# plant.net
KiCad netlist of a schematic drawn in EAGLE
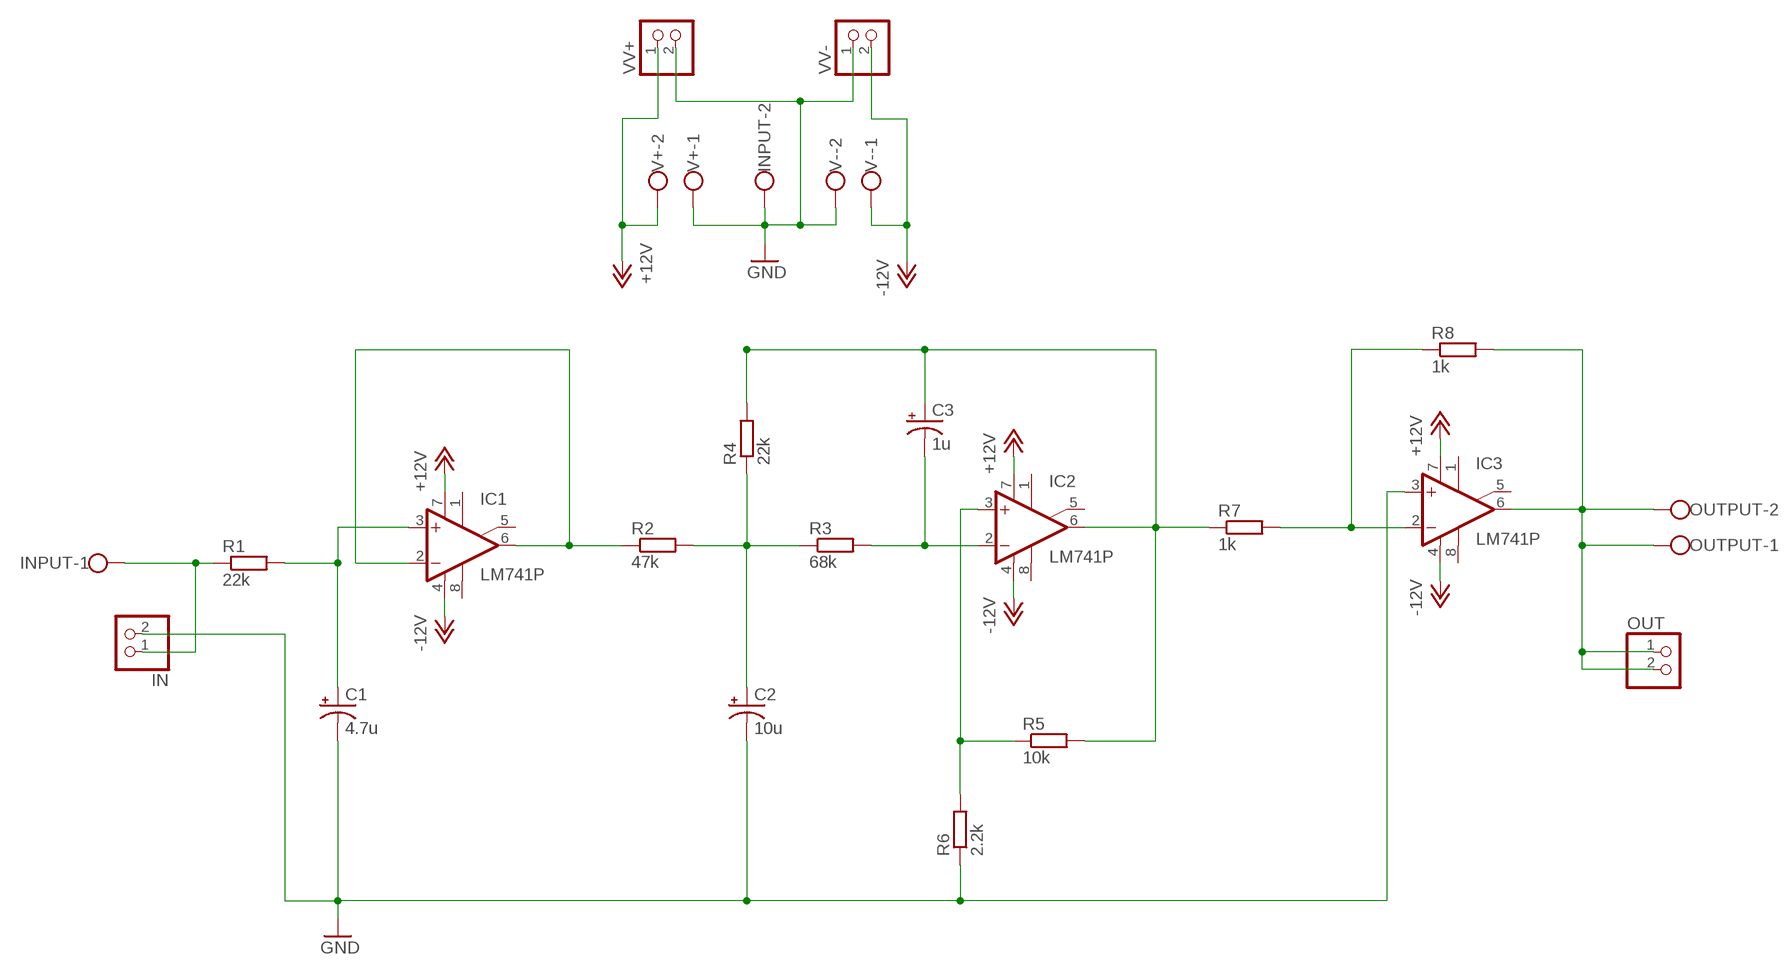
[diagram p0: schematic, sheet 1]

(export (version "E")
  (design (tool "Eeschema 10.0.6"))
  (components
    (comp (ref "C1")
      (value "4.7u")
      (footprint "eagle-import:E2,5-6")
      (libsource (lib "eagle-import") (part "CPOL-USE2.5-6"))
    )
    (comp (ref "C2")
      (value "10u")
      (footprint "eagle-import:E2,5-6")
      (libsource (lib "eagle-import") (part "CPOL-USE2.5-6"))
    )
    (comp (ref "C3")
      (value "1u")
      (footprint "eagle-import:E2,5-6")
      (libsource (lib "eagle-import") (part "CPOL-USE2.5-6"))
    )
    (comp (ref "IC1")
      (value "LM741P")
      (footprint "eagle-import:DIL08")
      (libsource (lib "eagle-import") (part "741PLM"))
    )
    (comp (ref "IC2")
      (value "LM741P")
      (footprint "eagle-import:DIL08")
      (libsource (lib "eagle-import") (part "741PLM"))
    )
    (comp (ref "IC3")
      (value "LM741P")
      (footprint "eagle-import:DIL08")
      (libsource (lib "eagle-import") (part "741PLM"))
    )
    (comp (ref "IN")
      (value "PINHD-1X2")
      (footprint "eagle-import:1X02")
      (libsource (lib "eagle-import") (part "PINHD-1X2"))
    )
    (comp (ref "INPUT")
      (value "W237-102")
      (footprint "eagle-import:W237-102")
      (fields (field (name "MPN") "237-102"))
      (libsource (lib "eagle-import") (part "W237-102"))
    )
    (comp (ref "OUT")
      (value "PINHD-1X2")
      (footprint "eagle-import:1X02")
      (libsource (lib "eagle-import") (part "PINHD-1X2"))
    )
    (comp (ref "OUTPUT")
      (value "W237-102")
      (footprint "eagle-import:W237-102")
      (fields (field (name "MPN") "237-102"))
      (libsource (lib "eagle-import") (part "W237-102"))
    )
    (comp (ref "R1")
      (value "22k")
      (footprint "eagle-import:0207_7")
      (libsource (lib "eagle-import") (part "R-EU_0207/7"))
    )
    (comp (ref "R2")
      (value "47k")
      (footprint "eagle-import:0207_7")
      (libsource (lib "eagle-import") (part "R-EU_0207/7"))
    )
    (comp (ref "R3")
      (value "68k")
      (footprint "eagle-import:0207_7")
      (libsource (lib "eagle-import") (part "R-EU_0207/7"))
    )
    (comp (ref "R4")
      (value "22k")
      (footprint "eagle-import:0207_7")
      (libsource (lib "eagle-import") (part "R-EU_0207/7"))
    )
    (comp (ref "R5")
      (value "10k")
      (footprint "eagle-import:0207_7")
      (libsource (lib "eagle-import") (part "R-EU_0207/7"))
    )
    (comp (ref "R6")
      (value "2.2k")
      (footprint "eagle-import:0207_7")
      (libsource (lib "eagle-import") (part "R-EU_0207/7"))
    )
    (comp (ref "R7")
      (value "1k")
      (footprint "eagle-import:0207_7")
      (libsource (lib "eagle-import") (part "R-EU_0207/7"))
    )
    (comp (ref "R8")
      (value "1k")
      (footprint "eagle-import:0207_7")
      (libsource (lib "eagle-import") (part "R-EU_0207/7"))
    )
    (comp (ref "V+")
      (value "W237-102")
      (footprint "eagle-import:W237-102")
      (fields (field (name "MPN") "237-102"))
      (libsource (lib "eagle-import") (part "W237-102"))
    )
    (comp (ref "V-")
      (value "W237-102")
      (footprint "eagle-import:W237-102")
      (fields (field (name "MPN") "237-102"))
      (libsource (lib "eagle-import") (part "W237-102"))
    )
    (comp (ref "VV+")
      (value "PINHD-1X2")
      (footprint "eagle-import:1X02")
      (libsource (lib "eagle-import") (part "PINHD-1X2"))
    )
    (comp (ref "VV-")
      (value "PINHD-1X2")
      (footprint "eagle-import:1X02")
      (libsource (lib "eagle-import") (part "PINHD-1X2"))
    )
  )
  (nets
    (net (code "1") (name "+12V") (class "Default")
      (node (ref "IC1") (pin "7") (pinfunction "V+_7") (pintype "power_in"))
      (node (ref "IC2") (pin "7") (pinfunction "V+_7") (pintype "power_in"))
      (node (ref "IC3") (pin "7") (pinfunction "V+_7") (pintype "power_in"))
      (node (ref "V+") (pin "2") (pinfunction "KL_2") (pintype "passive"))
      (node (ref "VV+") (pin "1") (pinfunction "1_1") (pintype "passive"))
    )
    (net (code "2") (name "-12V") (class "Default")
      (node (ref "IC1") (pin "4") (pinfunction "V-_4") (pintype "power_in"))
      (node (ref "IC2") (pin "4") (pinfunction "V-_4") (pintype "power_in"))
      (node (ref "IC3") (pin "4") (pinfunction "V-_4") (pintype "power_in"))
      (node (ref "V-") (pin "1") (pinfunction "KL_1") (pintype "passive"))
      (node (ref "VV-") (pin "2") (pinfunction "2_2") (pintype "passive"))
    )
    (net (code "3") (name "GND") (class "Default")
      (node (ref "C1") (pin "-") (pinfunction "-_-") (pintype "passive"))
      (node (ref "C2") (pin "-") (pinfunction "-_-") (pintype "passive"))
      (node (ref "IC3") (pin "3") (pinfunction "+IN_3") (pintype "input"))
      (node (ref "IN") (pin "2") (pinfunction "2_2") (pintype "passive"))
      (node (ref "INPUT") (pin "2") (pinfunction "KL_2") (pintype "passive"))
      (node (ref "R6") (pin "1") (pinfunction "1_1") (pintype "passive"))
      (node (ref "V+") (pin "1") (pinfunction "KL_1") (pintype "passive"))
      (node (ref "V-") (pin "2") (pinfunction "KL_2") (pintype "passive"))
      (node (ref "VV+") (pin "2") (pinfunction "2_2") (pintype "passive"))
      (node (ref "VV-") (pin "1") (pinfunction "1_1") (pintype "passive"))
    )
    (net (code "4") (name "Net-(C2-Pad+)") (class "Default")
      (node (ref "C2") (pin "+") (pinfunction "+_+") (pintype "passive"))
      (node (ref "R2") (pin "2") (pinfunction "2_2") (pintype "passive"))
      (node (ref "R3") (pin "1") (pinfunction "1_1") (pintype "passive"))
      (node (ref "R4") (pin "1") (pinfunction "1_1") (pintype "passive"))
    )
    (net (code "5") (name "Net-(IC1-+IN)") (class "Default")
      (node (ref "C1") (pin "+") (pinfunction "+_+") (pintype "passive"))
      (node (ref "IC1") (pin "3") (pinfunction "+IN_3") (pintype "input"))
      (node (ref "R1") (pin "2") (pinfunction "2_2") (pintype "passive"))
    )
    (net (code "6") (name "Net-(IC1--IN)") (class "Default")
      (node (ref "IC1") (pin "2") (pinfunction "-IN_2") (pintype "input"))
      (node (ref "IC1") (pin "6") (pinfunction "OUT_6") (pintype "output"))
      (node (ref "R2") (pin "1") (pinfunction "1_1") (pintype "passive"))
    )
    (net (code "7") (name "Net-(IC2-+IN)") (class "Default")
      (node (ref "IC2") (pin "3") (pinfunction "+IN_3") (pintype "input"))
      (node (ref "R5") (pin "1") (pinfunction "1_1") (pintype "passive"))
      (node (ref "R6") (pin "2") (pinfunction "2_2") (pintype "passive"))
    )
    (net (code "8") (name "Net-(IC2--IN)") (class "Default")
      (node (ref "C3") (pin "-") (pinfunction "-_-") (pintype "passive"))
      (node (ref "IC2") (pin "2") (pinfunction "-IN_2") (pintype "input"))
      (node (ref "R3") (pin "2") (pinfunction "2_2") (pintype "passive"))
    )
    (net (code "9") (name "Net-(IC2-OUT)") (class "Default")
      (node (ref "C3") (pin "+") (pinfunction "+_+") (pintype "passive"))
      (node (ref "IC2") (pin "6") (pinfunction "OUT_6") (pintype "output"))
      (node (ref "R4") (pin "2") (pinfunction "2_2") (pintype "passive"))
      (node (ref "R5") (pin "2") (pinfunction "2_2") (pintype "passive"))
      (node (ref "R7") (pin "1") (pinfunction "1_1") (pintype "passive"))
    )
    (net (code "10") (name "Net-(IC3--IN)") (class "Default")
      (node (ref "IC3") (pin "2") (pinfunction "-IN_2") (pintype "input"))
      (node (ref "R7") (pin "2") (pinfunction "2_2") (pintype "passive"))
      (node (ref "R8") (pin "1") (pinfunction "1_1") (pintype "passive"))
    )
    (net (code "11") (name "Net-(IC3-OUT)") (class "Default")
      (node (ref "IC3") (pin "6") (pinfunction "OUT_6") (pintype "output"))
      (node (ref "OUT") (pin "1") (pinfunction "1_1") (pintype "passive"))
      (node (ref "OUT") (pin "2") (pinfunction "2_2") (pintype "passive"))
      (node (ref "OUTPUT") (pin "1") (pinfunction "KL_1") (pintype "passive"))
      (node (ref "OUTPUT") (pin "2") (pinfunction "KL_2") (pintype "passive"))
      (node (ref "R8") (pin "2") (pinfunction "2_2") (pintype "passive"))
    )
    (net (code "12") (name "Net-(INPUTA-KL)") (class "Default")
      (node (ref "IN") (pin "1") (pinfunction "1_1") (pintype "passive"))
      (node (ref "INPUT") (pin "1") (pinfunction "KL_1") (pintype "passive"))
      (node (ref "R1") (pin "1") (pinfunction "1_1") (pintype "passive"))
    )
    (net (code "13") (name "unconnected-(IC1-ON1-Pad1)") (class "Default")
      (node (ref "IC1") (pin "1") (pinfunction "ON1_1") (pintype "passive"))
    )
    (net (code "14") (name "unconnected-(IC1-ON2-Pad5)") (class "Default")
      (node (ref "IC1") (pin "5") (pinfunction "ON2_5") (pintype "passive"))
    )
    (net (code "15") (name "unconnected-(IC1-OPT-Pad8)") (class "Default")
      (node (ref "IC1") (pin "8") (pinfunction "OPT_8") (pintype "passive"))
    )
    (net (code "16") (name "unconnected-(IC2-ON1-Pad1)") (class "Default")
      (node (ref "IC2") (pin "1") (pinfunction "ON1_1") (pintype "passive"))
    )
    (net (code "17") (name "unconnected-(IC2-ON2-Pad5)") (class "Default")
      (node (ref "IC2") (pin "5") (pinfunction "ON2_5") (pintype "passive"))
    )
    (net (code "18") (name "unconnected-(IC2-OPT-Pad8)") (class "Default")
      (node (ref "IC2") (pin "8") (pinfunction "OPT_8") (pintype "passive"))
    )
    (net (code "19") (name "unconnected-(IC3-ON1-Pad1)") (class "Default")
      (node (ref "IC3") (pin "1") (pinfunction "ON1_1") (pintype "passive"))
    )
    (net (code "20") (name "unconnected-(IC3-ON2-Pad5)") (class "Default")
      (node (ref "IC3") (pin "5") (pinfunction "ON2_5") (pintype "passive"))
    )
    (net (code "21") (name "unconnected-(IC3-OPT-Pad8)") (class "Default")
      (node (ref "IC3") (pin "8") (pinfunction "OPT_8") (pintype "passive"))
    )
  )
)
